# OC2.net
KiCad netlist of a schematic drawn in EAGLE
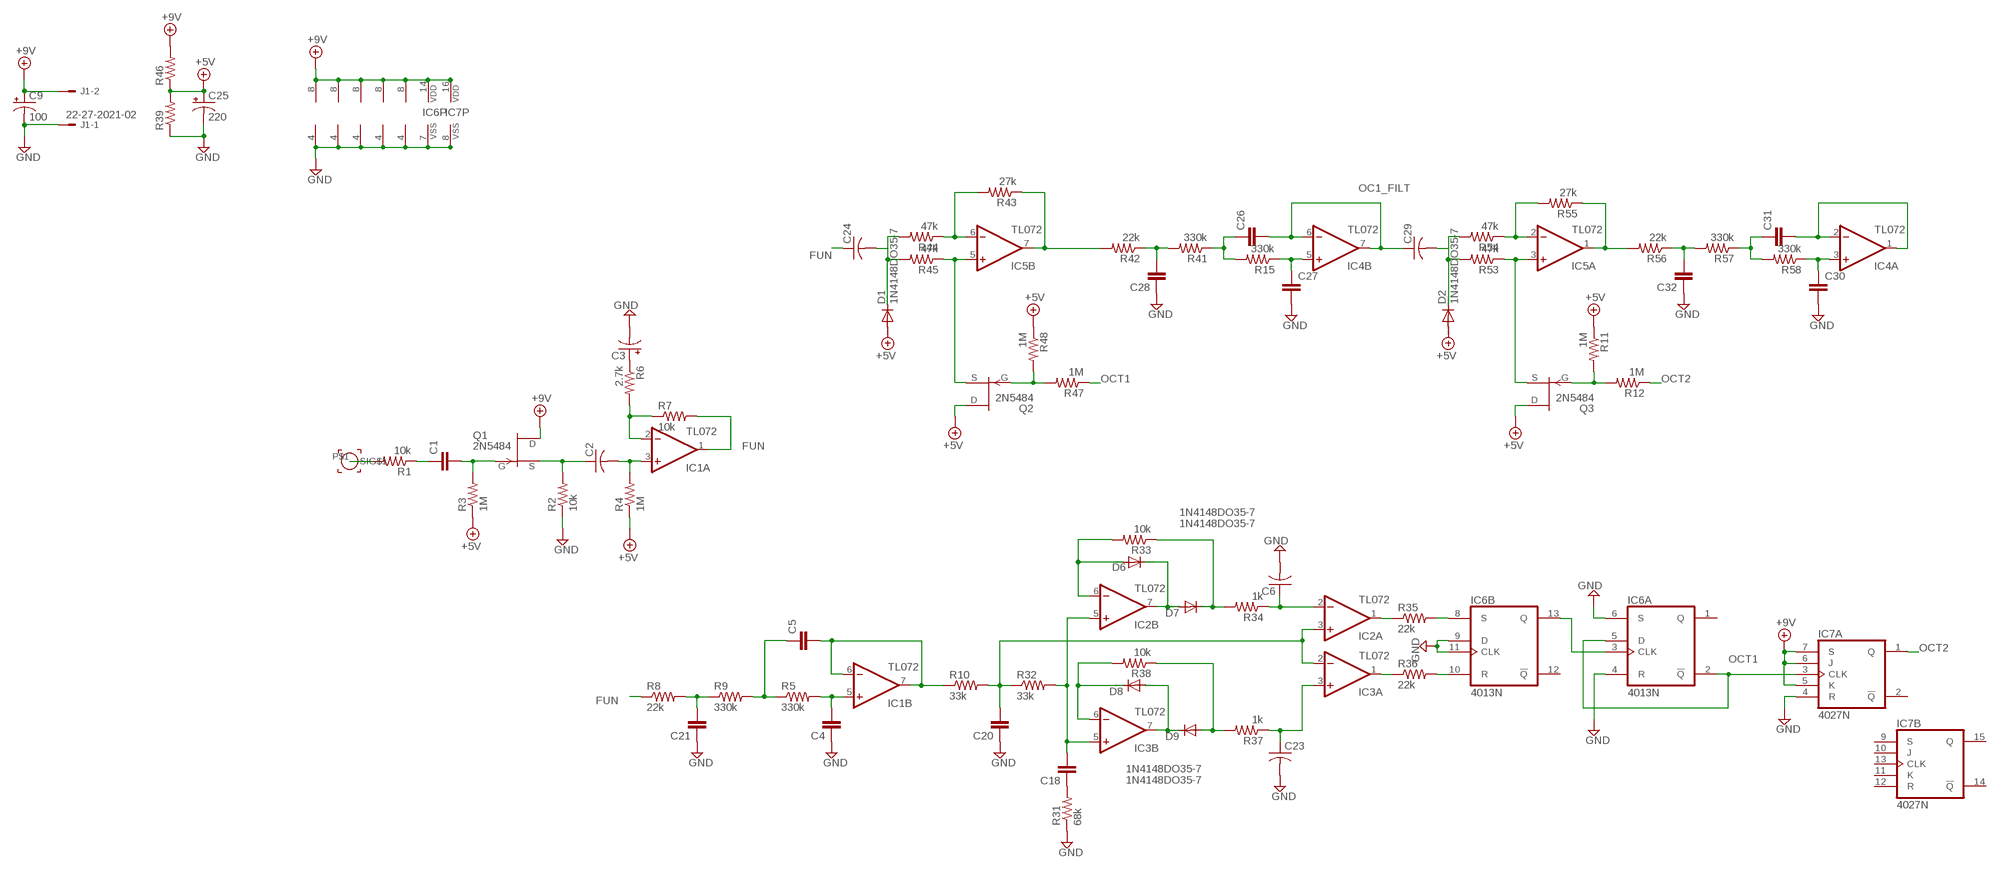
[diagram p0: schematic, sheet 1]

(export (version "E")
  (design (tool "Eeschema 10.0.6"))
  (components
    (comp (ref "C1")
      (value "C-EU")
      (footprint "eagle-import:C025-025X050-BP")
      (libsource (lib "eagle-import") (part "C-EU"))
    )
    (comp (ref "C2")
      (value "C-US")
      (footprint "eagle-import:C050-024X044-BP")
      (libsource (lib "eagle-import") (part "C-US"))
    )
    (comp (ref "C3")
      (value "CPOL-USE2.5-5")
      (footprint "eagle-import:E2,5-5")
      (libsource (lib "eagle-import") (part "CPOL-USE2.5-5"))
    )
    (comp (ref "C4")
      (value "C-EU")
      (footprint "eagle-import:C025-025X050-BP")
      (libsource (lib "eagle-import") (part "C-EU"))
    )
    (comp (ref "C5")
      (value "C-EU")
      (footprint "eagle-import:C025-025X050-BP")
      (libsource (lib "eagle-import") (part "C-EU"))
    )
    (comp (ref "C6")
      (value "C-US")
      (footprint "eagle-import:C050-024X044-BP")
      (libsource (lib "eagle-import") (part "C-US"))
    )
    (comp (ref "C9")
      (value "100")
      (footprint "eagle-import:E2,5-6")
      (libsource (lib "eagle-import") (part "CPOL-USE2.5-6"))
    )
    (comp (ref "C18")
      (value "C-EU")
      (footprint "eagle-import:C025-025X050-BP")
      (libsource (lib "eagle-import") (part "C-EU"))
    )
    (comp (ref "C20")
      (value "C-EU")
      (footprint "eagle-import:C025-025X050-BP")
      (libsource (lib "eagle-import") (part "C-EU"))
    )
    (comp (ref "C21")
      (value "C-EU")
      (footprint "eagle-import:C025-025X050-BP")
      (libsource (lib "eagle-import") (part "C-EU"))
    )
    (comp (ref "C23")
      (value "C-US")
      (footprint "eagle-import:C050-024X044-BP")
      (libsource (lib "eagle-import") (part "C-US"))
    )
    (comp (ref "C24")
      (value "C-US")
      (footprint "eagle-import:C050-024X044-BP")
      (libsource (lib "eagle-import") (part "C-US"))
    )
    (comp (ref "C25")
      (value "220")
      (footprint "eagle-import:E3,5-8")
      (libsource (lib "eagle-import") (part "CPOL-USE3.5-8"))
    )
    (comp (ref "C26")
      (value "C-EU")
      (footprint "eagle-import:C025-025X050-BP")
      (libsource (lib "eagle-import") (part "C-EU"))
    )
    (comp (ref "C27")
      (value "C-EU")
      (footprint "eagle-import:C025-025X050-BP")
      (libsource (lib "eagle-import") (part "C-EU"))
    )
    (comp (ref "C28")
      (value "C-EU")
      (footprint "eagle-import:C025-025X050-BP")
      (libsource (lib "eagle-import") (part "C-EU"))
    )
    (comp (ref "C29")
      (value "C-US")
      (footprint "eagle-import:C050-024X044-BP")
      (libsource (lib "eagle-import") (part "C-US"))
    )
    (comp (ref "C30")
      (value "C-EU")
      (footprint "eagle-import:C025-025X050-BP")
      (libsource (lib "eagle-import") (part "C-EU"))
    )
    (comp (ref "C31")
      (value "C-EU")
      (footprint "eagle-import:C025-025X050-BP")
      (libsource (lib "eagle-import") (part "C-EU"))
    )
    (comp (ref "C32")
      (value "C-EU")
      (footprint "eagle-import:C025-025X050-BP")
      (libsource (lib "eagle-import") (part "C-EU"))
    )
    (comp (ref "D1")
      (value "1N4148DO35-7")
      (footprint "eagle-import:DO35-7")
      (libsource (lib "eagle-import") (part "1N4148DO35-7"))
    )
    (comp (ref "D2")
      (value "1N4148DO35-7")
      (footprint "eagle-import:DO35-7")
      (libsource (lib "eagle-import") (part "1N4148DO35-7"))
    )
    (comp (ref "D6")
      (value "1N4148DO35-7")
      (footprint "eagle-import:DO35-7")
      (libsource (lib "eagle-import") (part "1N4148DO35-7"))
    )
    (comp (ref "D7")
      (value "1N4148DO35-7")
      (footprint "eagle-import:DO35-7")
      (libsource (lib "eagle-import") (part "1N4148DO35-7"))
    )
    (comp (ref "D8")
      (value "1N4148DO35-7")
      (footprint "eagle-import:DO35-7")
      (libsource (lib "eagle-import") (part "1N4148DO35-7"))
    )
    (comp (ref "D9")
      (value "1N4148DO35-7")
      (footprint "eagle-import:DO35-7")
      (libsource (lib "eagle-import") (part "1N4148DO35-7"))
    )
    (comp (ref "IC1")
      (value "TL072")
      (footprint "eagle-import:DIL08-BP")
      (libsource (lib "eagle-import") (part "TL072"))
    )
    (comp (ref "IC2")
      (value "TL072")
      (footprint "eagle-import:DIL08-BP")
      (libsource (lib "eagle-import") (part "TL072"))
    )
    (comp (ref "IC3")
      (value "TL072")
      (footprint "eagle-import:DIL08-BP")
      (libsource (lib "eagle-import") (part "TL072"))
    )
    (comp (ref "IC4")
      (value "TL072")
      (footprint "eagle-import:DIL08-BP")
      (libsource (lib "eagle-import") (part "TL072"))
    )
    (comp (ref "IC5")
      (value "TL072")
      (footprint "eagle-import:DIL08-BP")
      (libsource (lib "eagle-import") (part "TL072"))
    )
    (comp (ref "IC6")
      (value "4013N")
      (footprint "eagle-import:DIL14")
      (libsource (lib "eagle-import") (part "4013N"))
    )
    (comp (ref "IC7")
      (value "4027N")
      (footprint "eagle-import:DIL16")
      (libsource (lib "eagle-import") (part "4027N"))
    )
    (comp (ref "INPUT")
      (value "SIGNAL_PAD")
      (footprint "eagle-import:SIGNAL_PAD")
      (libsource (lib "eagle-import") (part "SIGNAL_PAD"))
    )
    (comp (ref "J1")
      (value "22-27-2021-02")
      (footprint "eagle-import:6410-02")
      (libsource (lib "eagle-import") (part "22-?-0227-2021"))
    )
    (comp (ref "Q1")
      (value "2N5484")
      (footprint "eagle-import:TO92-")
      (libsource (lib "eagle-import") (part "?5482N4"))
    )
    (comp (ref "Q2")
      (value "2N5484")
      (footprint "eagle-import:TO92-")
      (libsource (lib "eagle-import") (part "?5482N4"))
    )
    (comp (ref "Q3")
      (value "2N5484")
      (footprint "eagle-import:TO92-")
      (libsource (lib "eagle-import") (part "?5482N4"))
    )
    (comp (ref "R1")
      (value "10k")
      (footprint "eagle-import:0204V-BP")
      (libsource (lib "eagle-import") (part "R-US_"))
    )
    (comp (ref "R2")
      (value "10k")
      (footprint "eagle-import:0204V-BP")
      (libsource (lib "eagle-import") (part "R-US_"))
    )
    (comp (ref "R3")
      (value "1M")
      (footprint "eagle-import:0204V-BP")
      (libsource (lib "eagle-import") (part "R-US_"))
    )
    (comp (ref "R4")
      (value "1M")
      (footprint "eagle-import:0204V-BP")
      (libsource (lib "eagle-import") (part "R-US_"))
    )
    (comp (ref "R5")
      (value "330k")
      (footprint "eagle-import:0204V-BP")
      (libsource (lib "eagle-import") (part "R-US_"))
    )
    (comp (ref "R6")
      (value "2.7k")
      (footprint "eagle-import:0204V-BP")
      (libsource (lib "eagle-import") (part "R-US_"))
    )
    (comp (ref "R7")
      (value "10k")
      (footprint "eagle-import:0204V-BP")
      (libsource (lib "eagle-import") (part "R-US_"))
    )
    (comp (ref "R8")
      (value "22k")
      (footprint "eagle-import:0204V")
      (libsource (lib "eagle-import") (part "R-US_0204/2V"))
    )
    (comp (ref "R9")
      (value "330k")
      (footprint "eagle-import:0204_5")
      (libsource (lib "eagle-import") (part "R-US_0204/5"))
    )
    (comp (ref "R10")
      (value "33k")
      (footprint "eagle-import:0204V-BP")
      (libsource (lib "eagle-import") (part "R-US_"))
    )
    (comp (ref "R11")
      (value "1M")
      (footprint "eagle-import:0204V-BP")
      (libsource (lib "eagle-import") (part "R-US_"))
    )
    (comp (ref "R12")
      (value "1M")
      (footprint "eagle-import:0204V-BP")
      (libsource (lib "eagle-import") (part "R-US_"))
    )
    (comp (ref "R15")
      (value "330k")
      (footprint "eagle-import:0204V-BP")
      (libsource (lib "eagle-import") (part "R-US_"))
    )
    (comp (ref "R31")
      (value "68k")
      (footprint "eagle-import:0204V-BP")
      (libsource (lib "eagle-import") (part "R-US_"))
    )
    (comp (ref "R32")
      (value "33k")
      (footprint "eagle-import:0204V-BP")
      (libsource (lib "eagle-import") (part "R-US_"))
    )
    (comp (ref "R33")
      (value "10k")
      (footprint "eagle-import:0204V-BP")
      (libsource (lib "eagle-import") (part "R-US_"))
    )
    (comp (ref "R34")
      (value "1k")
      (footprint "eagle-import:0204V-BP")
      (libsource (lib "eagle-import") (part "R-US_"))
    )
    (comp (ref "R35")
      (value "22k")
      (footprint "eagle-import:0204V-BP")
      (libsource (lib "eagle-import") (part "R-US_"))
    )
    (comp (ref "R36")
      (value "22k")
      (footprint "eagle-import:0204_5")
      (libsource (lib "eagle-import") (part "R-US_0204/5"))
    )
    (comp (ref "R37")
      (value "1k")
      (footprint "eagle-import:0204V-BP")
      (libsource (lib "eagle-import") (part "R-US_"))
    )
    (comp (ref "R38")
      (value "10k")
      (footprint "eagle-import:0204V-BP")
      (libsource (lib "eagle-import") (part "R-US_"))
    )
    (comp (ref "R39")
      (value "R-US_")
      (footprint "eagle-import:0204V-BP")
      (libsource (lib "eagle-import") (part "R-US_"))
    )
    (comp (ref "R41")
      (value "330k")
      (footprint "eagle-import:0204V-BP")
      (libsource (lib "eagle-import") (part "R-US_"))
    )
    (comp (ref "R42")
      (value "22k")
      (footprint "eagle-import:0204V-BP")
      (libsource (lib "eagle-import") (part "R-US_"))
    )
    (comp (ref "R43")
      (value "27k")
      (footprint "eagle-import:0204V-BP")
      (libsource (lib "eagle-import") (part "R-US_"))
    )
    (comp (ref "R44")
      (value "47k")
      (footprint "eagle-import:0204V-BP")
      (libsource (lib "eagle-import") (part "R-US_"))
    )
    (comp (ref "R45")
      (value "47k")
      (footprint "eagle-import:0204V-BP")
      (libsource (lib "eagle-import") (part "R-US_"))
    )
    (comp (ref "R46")
      (value "R-US_")
      (footprint "eagle-import:0204V-BP")
      (libsource (lib "eagle-import") (part "R-US_"))
    )
    (comp (ref "R47")
      (value "1M")
      (footprint "eagle-import:0204V-BP")
      (libsource (lib "eagle-import") (part "R-US_"))
    )
    (comp (ref "R48")
      (value "1M")
      (footprint "eagle-import:0204V-BP")
      (libsource (lib "eagle-import") (part "R-US_"))
    )
    (comp (ref "R53")
      (value "47k")
      (footprint "eagle-import:0204V-BP")
      (libsource (lib "eagle-import") (part "R-US_"))
    )
    (comp (ref "R54")
      (value "47k")
      (footprint "eagle-import:0204V-BP")
      (libsource (lib "eagle-import") (part "R-US_"))
    )
    (comp (ref "R55")
      (value "27k")
      (footprint "eagle-import:0204V-BP")
      (libsource (lib "eagle-import") (part "R-US_"))
    )
    (comp (ref "R56")
      (value "22k")
      (footprint "eagle-import:0204V-BP")
      (libsource (lib "eagle-import") (part "R-US_"))
    )
    (comp (ref "R57")
      (value "330k")
      (footprint "eagle-import:0204V-BP")
      (libsource (lib "eagle-import") (part "R-US_"))
    )
    (comp (ref "R58")
      (value "330k")
      (footprint "eagle-import:0204V-BP")
      (libsource (lib "eagle-import") (part "R-US_"))
    )
  )
  (nets
    (net (code "1") (name "+5V") (class "Default")
      (node (ref "C25") (pin "+") (pinfunction "+_+") (pintype "passive"))
      (node (ref "D1") (pin "A") (pinfunction "A_A") (pintype "passive"))
      (node (ref "D2") (pin "A") (pinfunction "A_A") (pintype "passive"))
      (node (ref "Q2") (pin "3") (pinfunction "D_3") (pintype "passive"))
      (node (ref "Q3") (pin "3") (pinfunction "D_3") (pintype "passive"))
      (node (ref "R11") (pin "1") (pinfunction "1_1") (pintype "passive"))
      (node (ref "R3") (pin "1") (pinfunction "1_1") (pintype "passive"))
      (node (ref "R39") (pin "2") (pinfunction "2_2") (pintype "passive"))
      (node (ref "R4") (pin "1") (pinfunction "1_1") (pintype "passive"))
      (node (ref "R46") (pin "1") (pinfunction "1_1") (pintype "passive"))
      (node (ref "R48") (pin "1") (pinfunction "1_1") (pintype "passive"))
    )
    (net (code "2") (name "+9V") (class "Default")
      (node (ref "C9") (pin "+") (pinfunction "+_+") (pintype "passive"))
      (node (ref "IC1") (pin "8") (pinfunction "V+_8") (pintype "power_in"))
      (node (ref "IC2") (pin "8") (pinfunction "V+_8") (pintype "power_in"))
      (node (ref "IC3") (pin "8") (pinfunction "V+_8") (pintype "power_in"))
      (node (ref "IC4") (pin "8") (pinfunction "V+_8") (pintype "power_in"))
      (node (ref "IC5") (pin "8") (pinfunction "V+_8") (pintype "power_in"))
      (node (ref "IC6") (pin "14") (pinfunction "VDD_14") (pintype "power_in"))
      (node (ref "IC7") (pin "16") (pinfunction "VDD_16") (pintype "power_in"))
      (node (ref "IC7") (pin "5") (pinfunction "K_5") (pintype "input"))
      (node (ref "IC7") (pin "6") (pinfunction "J_6") (pintype "input"))
      (node (ref "IC7") (pin "7") (pinfunction "S_7") (pintype "input"))
      (node (ref "J1") (pin "2") (pinfunction "S_2") (pintype "passive"))
      (node (ref "Q1") (pin "3") (pinfunction "D_3") (pintype "passive"))
      (node (ref "R46") (pin "2") (pinfunction "2_2") (pintype "passive"))
    )
    (net (code "3") (name "/FUN") (class "Default")
      (node (ref "C24") (pin "1") (pinfunction "1_1") (pintype "passive"))
      (node (ref "IC1") (pin "1") (pinfunction "OUT_1") (pintype "output"))
      (node (ref "R7") (pin "2") (pinfunction "2_2") (pintype "passive"))
      (node (ref "R8") (pin "1") (pinfunction "1_1") (pintype "passive"))
    )
    (net (code "4") (name "/OC1_FILT") (class "Default")
      (node (ref "C26") (pin "2") (pinfunction "2_2") (pintype "passive"))
      (node (ref "C29") (pin "1") (pinfunction "1_1") (pintype "passive"))
      (node (ref "IC4") (pin "6") (pinfunction "-IN_6") (pintype "input"))
      (node (ref "IC4") (pin "7") (pinfunction "OUT_7") (pintype "output"))
    )
    (net (code "5") (name "/OCT1") (class "Default")
      (node (ref "IC6") (pin "2") (pinfunction "~{Q}_2") (pintype "output"))
      (node (ref "IC6") (pin "5") (pinfunction "D_5") (pintype "input"))
      (node (ref "IC7") (pin "3") (pinfunction "CLK_3") (pintype "input"))
      (node (ref "R47") (pin "1") (pinfunction "1_1") (pintype "passive"))
    )
    (net (code "6") (name "/OCT2") (class "Default")
      (node (ref "IC7") (pin "1") (pinfunction "Q_1") (pintype "output"))
      (node (ref "R12") (pin "1") (pinfunction "1_1") (pintype "passive"))
    )
    (net (code "7") (name "GND") (class "Default")
      (node (ref "C20") (pin "1") (pinfunction "1_1") (pintype "passive"))
      (node (ref "C21") (pin "1") (pinfunction "1_1") (pintype "passive"))
      (node (ref "C23") (pin "2") (pinfunction "2_2") (pintype "passive"))
      (node (ref "C25") (pin "-") (pinfunction "-_-") (pintype "passive"))
      (node (ref "C27") (pin "2") (pinfunction "2_2") (pintype "passive"))
      (node (ref "C28") (pin "1") (pinfunction "1_1") (pintype "passive"))
      (node (ref "C3") (pin "-") (pinfunction "-_-") (pintype "passive"))
      (node (ref "C30") (pin "2") (pinfunction "2_2") (pintype "passive"))
      (node (ref "C32") (pin "1") (pinfunction "1_1") (pintype "passive"))
      (node (ref "C4") (pin "1") (pinfunction "1_1") (pintype "passive"))
      (node (ref "C6") (pin "2") (pinfunction "2_2") (pintype "passive"))
      (node (ref "C9") (pin "-") (pinfunction "-_-") (pintype "passive"))
      (node (ref "IC1") (pin "4") (pinfunction "V-_4") (pintype "power_in"))
      (node (ref "IC2") (pin "4") (pinfunction "V-_4") (pintype "power_in"))
      (node (ref "IC3") (pin "4") (pinfunction "V-_4") (pintype "power_in"))
      (node (ref "IC4") (pin "4") (pinfunction "V-_4") (pintype "power_in"))
      (node (ref "IC5") (pin "4") (pinfunction "V-_4") (pintype "power_in"))
      (node (ref "IC6") (pin "11") (pinfunction "CLK_11") (pintype "input"))
      (node (ref "IC6") (pin "4") (pinfunction "R_4") (pintype "input"))
      (node (ref "IC6") (pin "6") (pinfunction "S_6") (pintype "input"))
      (node (ref "IC6") (pin "7") (pinfunction "VSS_7") (pintype "power_in"))
      (node (ref "IC6") (pin "9") (pinfunction "D_9") (pintype "input"))
      (node (ref "IC7") (pin "4") (pinfunction "R_4") (pintype "input"))
      (node (ref "IC7") (pin "8") (pinfunction "VSS_8") (pintype "power_in"))
      (node (ref "J1") (pin "1") (pinfunction "S_1") (pintype "passive"))
      (node (ref "R2") (pin "1") (pinfunction "1_1") (pintype "passive"))
      (node (ref "R31") (pin "1") (pinfunction "1_1") (pintype "passive"))
      (node (ref "R39") (pin "1") (pinfunction "1_1") (pintype "passive"))
    )
    (net (code "8") (name "Net-(C1-Pad1)") (class "Default")
      (node (ref "C1") (pin "1") (pinfunction "1_1") (pintype "passive"))
      (node (ref "R1") (pin "1") (pinfunction "1_1") (pintype "passive"))
    )
    (net (code "9") (name "Net-(C3-Pad+)") (class "Default")
      (node (ref "C3") (pin "+") (pinfunction "+_+") (pintype "passive"))
      (node (ref "R6") (pin "1") (pinfunction "1_1") (pintype "passive"))
    )
    (net (code "10") (name "Net-(C5-Pad1)") (class "Default")
      (node (ref "C5") (pin "1") (pinfunction "1_1") (pintype "passive"))
      (node (ref "R5") (pin "1") (pinfunction "1_1") (pintype "passive"))
      (node (ref "R9") (pin "2") (pinfunction "2_2") (pintype "passive"))
    )
    (net (code "11") (name "Net-(C18-Pad1)") (class "Default")
      (node (ref "C18") (pin "1") (pinfunction "1_1") (pintype "passive"))
      (node (ref "R31") (pin "2") (pinfunction "2_2") (pintype "passive"))
    )
    (net (code "12") (name "Net-(C21-Pad2)") (class "Default")
      (node (ref "C21") (pin "2") (pinfunction "2_2") (pintype "passive"))
      (node (ref "R8") (pin "2") (pinfunction "2_2") (pintype "passive"))
      (node (ref "R9") (pin "1") (pinfunction "1_1") (pintype "passive"))
    )
    (net (code "13") (name "Net-(C24-Pad2)") (class "Default")
      (node (ref "C24") (pin "2") (pinfunction "2_2") (pintype "passive"))
      (node (ref "D1") (pin "C") (pinfunction "C_C") (pintype "passive"))
      (node (ref "R44") (pin "2") (pinfunction "2_2") (pintype "passive"))
      (node (ref "R45") (pin "2") (pinfunction "2_2") (pintype "passive"))
    )
    (net (code "14") (name "Net-(C26-Pad1)") (class "Default")
      (node (ref "C26") (pin "1") (pinfunction "1_1") (pintype "passive"))
      (node (ref "R15") (pin "2") (pinfunction "2_2") (pintype "passive"))
      (node (ref "R41") (pin "1") (pinfunction "1_1") (pintype "passive"))
    )
    (net (code "15") (name "Net-(C28-Pad2)") (class "Default")
      (node (ref "C28") (pin "2") (pinfunction "2_2") (pintype "passive"))
      (node (ref "R41") (pin "2") (pinfunction "2_2") (pintype "passive"))
      (node (ref "R42") (pin "1") (pinfunction "1_1") (pintype "passive"))
    )
    (net (code "16") (name "Net-(C29-Pad2)") (class "Default")
      (node (ref "C29") (pin "2") (pinfunction "2_2") (pintype "passive"))
      (node (ref "D2") (pin "C") (pinfunction "C_C") (pintype "passive"))
      (node (ref "R53") (pin "2") (pinfunction "2_2") (pintype "passive"))
      (node (ref "R54") (pin "2") (pinfunction "2_2") (pintype "passive"))
    )
    (net (code "17") (name "Net-(C31-Pad1)") (class "Default")
      (node (ref "C31") (pin "1") (pinfunction "1_1") (pintype "passive"))
      (node (ref "R57") (pin "1") (pinfunction "1_1") (pintype "passive"))
      (node (ref "R58") (pin "2") (pinfunction "2_2") (pintype "passive"))
    )
    (net (code "18") (name "Net-(C32-Pad2)") (class "Default")
      (node (ref "C32") (pin "2") (pinfunction "2_2") (pintype "passive"))
      (node (ref "R56") (pin "1") (pinfunction "1_1") (pintype "passive"))
      (node (ref "R57") (pin "2") (pinfunction "2_2") (pintype "passive"))
    )
    (net (code "19") (name "Net-(D7-PadC)") (class "Default")
      (node (ref "D7") (pin "C") (pinfunction "C_C") (pintype "passive"))
      (node (ref "R33") (pin "1") (pinfunction "1_1") (pintype "passive"))
      (node (ref "R34") (pin "2") (pinfunction "2_2") (pintype "passive"))
    )
    (net (code "20") (name "Net-(D9-PadA)") (class "Default")
      (node (ref "D9") (pin "A") (pinfunction "A_A") (pintype "passive"))
      (node (ref "R37") (pin "2") (pinfunction "2_2") (pintype "passive"))
      (node (ref "R38") (pin "1") (pinfunction "1_1") (pintype "passive"))
    )
    (net (code "21") (name "Net-(IC1A-+IN)") (class "Default")
      (node (ref "C2") (pin "2") (pinfunction "2_2") (pintype "passive"))
      (node (ref "IC1") (pin "3") (pinfunction "+IN_3") (pintype "input"))
      (node (ref "R4") (pin "2") (pinfunction "2_2") (pintype "passive"))
    )
    (net (code "22") (name "Net-(IC1A--IN)") (class "Default")
      (node (ref "IC1") (pin "2") (pinfunction "-IN_2") (pintype "input"))
      (node (ref "R6") (pin "2") (pinfunction "2_2") (pintype "passive"))
      (node (ref "R7") (pin "1") (pinfunction "1_1") (pintype "passive"))
    )
    (net (code "23") (name "Net-(IC1B-+IN)") (class "Default")
      (node (ref "C4") (pin "2") (pinfunction "2_2") (pintype "passive"))
      (node (ref "IC1") (pin "5") (pinfunction "+IN_5") (pintype "input"))
      (node (ref "R5") (pin "2") (pinfunction "2_2") (pintype "passive"))
    )
    (net (code "24") (name "Net-(IC1B--IN)") (class "Default")
      (node (ref "C5") (pin "2") (pinfunction "2_2") (pintype "passive"))
      (node (ref "IC1") (pin "6") (pinfunction "-IN_6") (pintype "input"))
      (node (ref "IC1") (pin "7") (pinfunction "OUT_7") (pintype "output"))
      (node (ref "R10") (pin "1") (pinfunction "1_1") (pintype "passive"))
    )
    (net (code "25") (name "Net-(IC2A-+IN)") (class "Default")
      (node (ref "C20") (pin "2") (pinfunction "2_2") (pintype "passive"))
      (node (ref "IC2") (pin "3") (pinfunction "+IN_3") (pintype "input"))
      (node (ref "IC3") (pin "2") (pinfunction "-IN_2") (pintype "input"))
      (node (ref "R10") (pin "2") (pinfunction "2_2") (pintype "passive"))
      (node (ref "R32") (pin "1") (pinfunction "1_1") (pintype "passive"))
    )
    (net (code "26") (name "Net-(IC2A--IN)") (class "Default")
      (node (ref "C6") (pin "1") (pinfunction "1_1") (pintype "passive"))
      (node (ref "IC2") (pin "2") (pinfunction "-IN_2") (pintype "input"))
      (node (ref "R34") (pin "1") (pinfunction "1_1") (pintype "passive"))
    )
    (net (code "27") (name "Net-(IC2A-OUT)") (class "Default")
      (node (ref "IC2") (pin "1") (pinfunction "OUT_1") (pintype "output"))
      (node (ref "R35") (pin "1") (pinfunction "1_1") (pintype "passive"))
    )
    (net (code "28") (name "Net-(IC2B-+IN)") (class "Default")
      (node (ref "C18") (pin "2") (pinfunction "2_2") (pintype "passive"))
      (node (ref "IC2") (pin "5") (pinfunction "+IN_5") (pintype "input"))
      (node (ref "IC3") (pin "5") (pinfunction "+IN_5") (pintype "input"))
      (node (ref "R32") (pin "2") (pinfunction "2_2") (pintype "passive"))
    )
    (net (code "29") (name "Net-(IC2B--IN)") (class "Default")
      (node (ref "D6") (pin "A") (pinfunction "A_A") (pintype "passive"))
      (node (ref "IC2") (pin "6") (pinfunction "-IN_6") (pintype "input"))
      (node (ref "R33") (pin "2") (pinfunction "2_2") (pintype "passive"))
    )
    (net (code "30") (name "Net-(IC2B-OUT)") (class "Default")
      (node (ref "D6") (pin "C") (pinfunction "C_C") (pintype "passive"))
      (node (ref "D7") (pin "A") (pinfunction "A_A") (pintype "passive"))
      (node (ref "IC2") (pin "7") (pinfunction "OUT_7") (pintype "output"))
    )
    (net (code "31") (name "Net-(IC3A-+IN)") (class "Default")
      (node (ref "C23") (pin "1") (pinfunction "1_1") (pintype "passive"))
      (node (ref "IC3") (pin "3") (pinfunction "+IN_3") (pintype "input"))
      (node (ref "R37") (pin "1") (pinfunction "1_1") (pintype "passive"))
    )
    (net (code "32") (name "Net-(IC3A-OUT)") (class "Default")
      (node (ref "IC3") (pin "1") (pinfunction "OUT_1") (pintype "output"))
      (node (ref "R36") (pin "1") (pinfunction "1_1") (pintype "passive"))
    )
    (net (code "33") (name "Net-(IC3B--IN)") (class "Default")
      (node (ref "D8") (pin "C") (pinfunction "C_C") (pintype "passive"))
      (node (ref "IC3") (pin "6") (pinfunction "-IN_6") (pintype "input"))
      (node (ref "R38") (pin "2") (pinfunction "2_2") (pintype "passive"))
    )
    (net (code "34") (name "Net-(IC3B-OUT)") (class "Default")
      (node (ref "D8") (pin "A") (pinfunction "A_A") (pintype "passive"))
      (node (ref "D9") (pin "C") (pinfunction "C_C") (pintype "passive"))
      (node (ref "IC3") (pin "7") (pinfunction "OUT_7") (pintype "output"))
    )
    (net (code "35") (name "Net-(IC4A-+IN)") (class "Default")
      (node (ref "C30") (pin "1") (pinfunction "1_1") (pintype "passive"))
      (node (ref "IC4") (pin "3") (pinfunction "+IN_3") (pintype "input"))
      (node (ref "R58") (pin "1") (pinfunction "1_1") (pintype "passive"))
    )
    (net (code "36") (name "Net-(IC4A--IN)") (class "Default")
      (node (ref "C31") (pin "2") (pinfunction "2_2") (pintype "passive"))
      (node (ref "IC4") (pin "1") (pinfunction "OUT_1") (pintype "output"))
      (node (ref "IC4") (pin "2") (pinfunction "-IN_2") (pintype "input"))
    )
    (net (code "37") (name "Net-(IC4B-+IN)") (class "Default")
      (node (ref "C27") (pin "1") (pinfunction "1_1") (pintype "passive"))
      (node (ref "IC4") (pin "5") (pinfunction "+IN_5") (pintype "input"))
      (node (ref "R15") (pin "1") (pinfunction "1_1") (pintype "passive"))
    )
    (net (code "38") (name "Net-(IC5A-+IN)") (class "Default")
      (node (ref "IC5") (pin "3") (pinfunction "+IN_3") (pintype "input"))
      (node (ref "Q3") (pin "2") (pinfunction "S_2") (pintype "passive"))
      (node (ref "R53") (pin "1") (pinfunction "1_1") (pintype "passive"))
    )
    (net (code "39") (name "Net-(IC5A--IN)") (class "Default")
      (node (ref "IC5") (pin "2") (pinfunction "-IN_2") (pintype "input"))
      (node (ref "R54") (pin "1") (pinfunction "1_1") (pintype "passive"))
      (node (ref "R55") (pin "2") (pinfunction "2_2") (pintype "passive"))
    )
    (net (code "40") (name "Net-(IC5A-OUT)") (class "Default")
      (node (ref "IC5") (pin "1") (pinfunction "OUT_1") (pintype "output"))
      (node (ref "R55") (pin "1") (pinfunction "1_1") (pintype "passive"))
      (node (ref "R56") (pin "2") (pinfunction "2_2") (pintype "passive"))
    )
    (net (code "41") (name "Net-(IC5B-+IN)") (class "Default")
      (node (ref "IC5") (pin "5") (pinfunction "+IN_5") (pintype "input"))
      (node (ref "Q2") (pin "2") (pinfunction "S_2") (pintype "passive"))
      (node (ref "R45") (pin "1") (pinfunction "1_1") (pintype "passive"))
    )
    (net (code "42") (name "Net-(IC5B--IN)") (class "Default")
      (node (ref "IC5") (pin "6") (pinfunction "-IN_6") (pintype "input"))
      (node (ref "R43") (pin "2") (pinfunction "2_2") (pintype "passive"))
      (node (ref "R44") (pin "1") (pinfunction "1_1") (pintype "passive"))
    )
    (net (code "43") (name "Net-(IC5B-OUT)") (class "Default")
      (node (ref "IC5") (pin "7") (pinfunction "OUT_7") (pintype "output"))
      (node (ref "R42") (pin "2") (pinfunction "2_2") (pintype "passive"))
      (node (ref "R43") (pin "1") (pinfunction "1_1") (pintype "passive"))
    )
    (net (code "44") (name "Net-(IC6A-CLK)") (class "Default")
      (node (ref "IC6") (pin "13") (pinfunction "Q_13") (pintype "output"))
      (node (ref "IC6") (pin "3") (pinfunction "CLK_3") (pintype "input"))
    )
    (net (code "45") (name "Net-(IC6B-R)") (class "Default")
      (node (ref "IC6") (pin "10") (pinfunction "R_10") (pintype "input"))
      (node (ref "R36") (pin "2") (pinfunction "2_2") (pintype "passive"))
    )
    (net (code "46") (name "Net-(IC6B-S)") (class "Default")
      (node (ref "IC6") (pin "8") (pinfunction "S_8") (pintype "input"))
      (node (ref "R35") (pin "2") (pinfunction "2_2") (pintype "passive"))
    )
    (net (code "47") (name "Net-(INPUT-SIG$1)") (class "Default")
      (node (ref "INPUT") (pin "P$1") (pinfunction "SIG$1_P$1") (pintype "bidirectional"))
      (node (ref "R1") (pin "2") (pinfunction "2_2") (pintype "passive"))
    )
    (net (code "48") (name "Net-(Q1-G)") (class "Default")
      (node (ref "C1") (pin "2") (pinfunction "2_2") (pintype "passive"))
      (node (ref "Q1") (pin "1") (pinfunction "G_1") (pintype "passive"))
      (node (ref "R3") (pin "2") (pinfunction "2_2") (pintype "passive"))
    )
    (net (code "49") (name "Net-(Q1-S)") (class "Default")
      (node (ref "C2") (pin "1") (pinfunction "1_1") (pintype "passive"))
      (node (ref "Q1") (pin "2") (pinfunction "S_2") (pintype "passive"))
      (node (ref "R2") (pin "2") (pinfunction "2_2") (pintype "passive"))
    )
    (net (code "50") (name "Net-(Q2-G)") (class "Default")
      (node (ref "Q2") (pin "1") (pinfunction "G_1") (pintype "passive"))
      (node (ref "R47") (pin "2") (pinfunction "2_2") (pintype "passive"))
      (node (ref "R48") (pin "2") (pinfunction "2_2") (pintype "passive"))
    )
    (net (code "51") (name "Net-(Q3-G)") (class "Default")
      (node (ref "Q3") (pin "1") (pinfunction "G_1") (pintype "passive"))
      (node (ref "R11") (pin "2") (pinfunction "2_2") (pintype "passive"))
      (node (ref "R12") (pin "2") (pinfunction "2_2") (pintype "passive"))
    )
    (net (code "52") (name "unconnected-(IC6A-Q-Pad1)") (class "Default")
      (node (ref "IC6") (pin "1") (pinfunction "Q_1") (pintype "output"))
    )
    (net (code "53") (name "unconnected-(IC6B-~{Q}-Pad12)") (class "Default")
      (node (ref "IC6") (pin "12") (pinfunction "~{Q}_12") (pintype "output"))
    )
    (net (code "54") (name "unconnected-(IC7A-~{Q}-Pad2)") (class "Default")
      (node (ref "IC7") (pin "2") (pinfunction "~{Q}_2") (pintype "output"))
    )
    (net (code "55") (name "unconnected-(IC7B-CLK-Pad13)") (class "Default")
      (node (ref "IC7") (pin "13") (pinfunction "CLK_13") (pintype "input"))
    )
    (net (code "56") (name "unconnected-(IC7B-J-Pad10)") (class "Default")
      (node (ref "IC7") (pin "10") (pinfunction "J_10") (pintype "input"))
    )
    (net (code "57") (name "unconnected-(IC7B-K-Pad11)") (class "Default")
      (node (ref "IC7") (pin "11") (pinfunction "K_11") (pintype "input"))
    )
    (net (code "58") (name "unconnected-(IC7B-Q-Pad15)") (class "Default")
      (node (ref "IC7") (pin "15") (pinfunction "Q_15") (pintype "output"))
    )
    (net (code "59") (name "unconnected-(IC7B-R-Pad12)") (class "Default")
      (node (ref "IC7") (pin "12") (pinfunction "R_12") (pintype "input"))
    )
    (net (code "60") (name "unconnected-(IC7B-S-Pad9)") (class "Default")
      (node (ref "IC7") (pin "9") (pinfunction "S_9") (pintype "input"))
    )
    (net (code "61") (name "unconnected-(IC7B-~{Q}-Pad14)") (class "Default")
      (node (ref "IC7") (pin "14") (pinfunction "~{Q}_14") (pintype "output"))
    )
  )
)
